# dpbv3_schematic.net
KiCad netlist of a schematic drawn in EasyEDA Pro
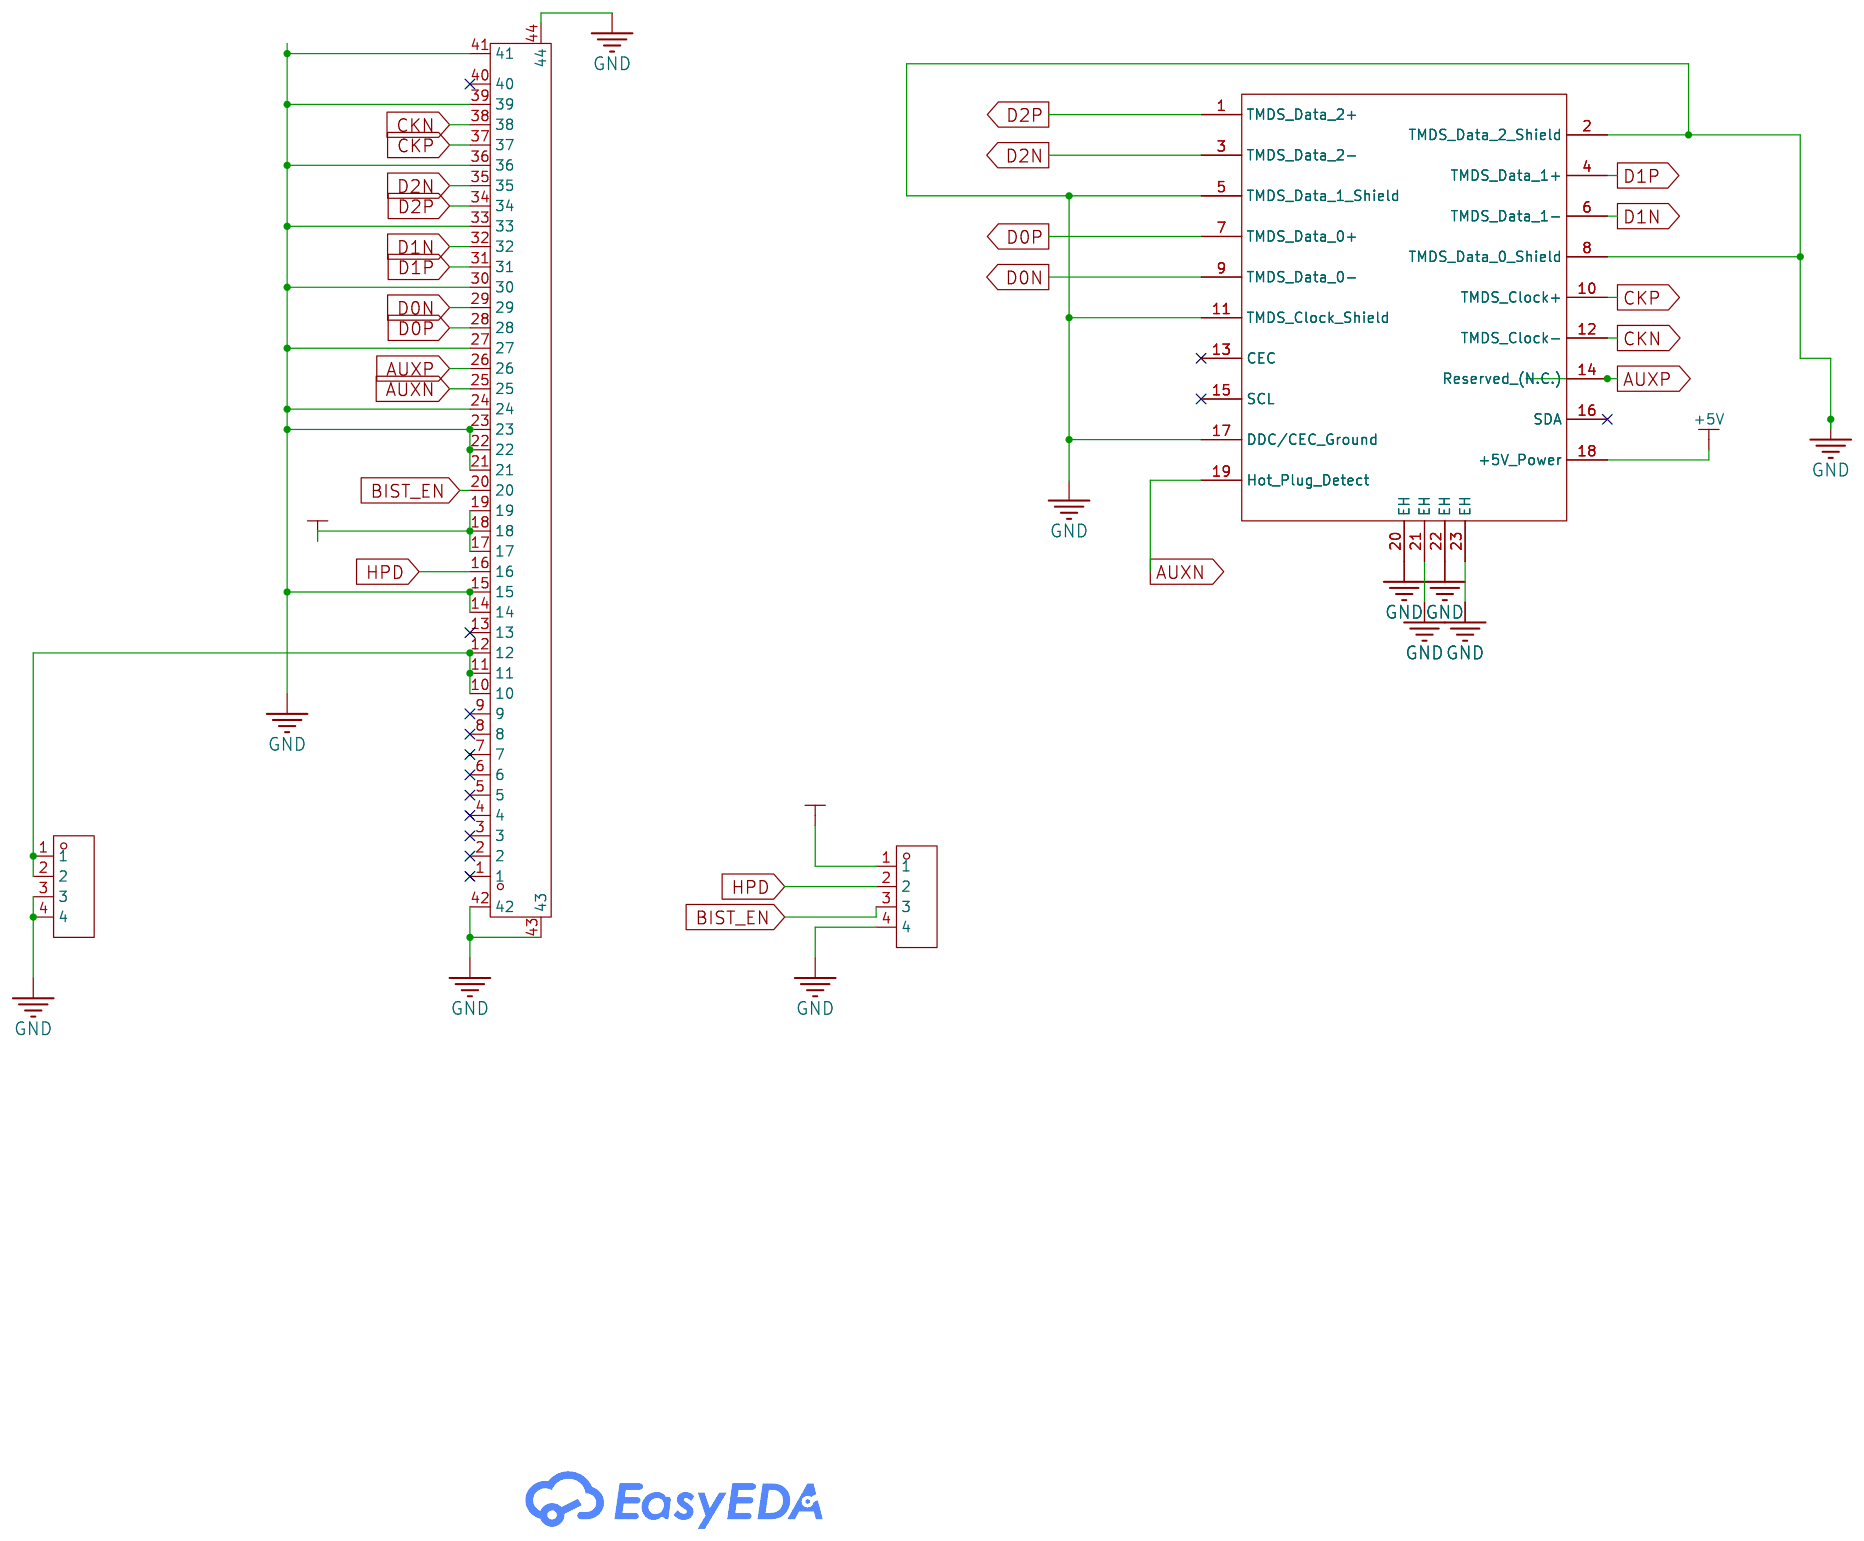
[diagram p0: schematic sheet]

(export (version "E")
  (design (tool "Eeschema 10.0.6"))
  (components
    (comp (ref "CN1")
      (value "20455-040E-76")
      (footprint "easyedapro:CONN-SMD_40P-P-0.50_20455-040E-76")
      (fields (field (name "Manufacturer") "I-PEX(第一精工)"))
      (libsource (lib "easyedapro") (part "20455-040E-76"))
    )
    (comp (ref "CN2")
      (value "HYC109-HDMIA19-160")
      (footprint "easyedapro:HDMI-SMD_HYC109-HDMIA19-160")
      (fields (field (name "Manufacturer") "华宇创"))
      (libsource (lib "easyedapro") (part "HYC109-HDMIA19-160"))
    )
    (comp (ref "H1")
      (value "PZ254V-11-04P")
      (footprint "easyedapro:HDR-TH_4P-P2.54-V-M")
      (fields (field (name "Manufacturer") "XFCN(兴飞)"))
      (libsource (lib "easyedapro") (part "PZ254V-11-04P_C2691448"))
    )
    (comp (ref "H2")
      (value "PZ254V-11-04P")
      (footprint "easyedapro:HDR-TH_4P-P2.54-V-M")
      (fields (field (name "Manufacturer") "XFCN(兴飞)"))
      (libsource (lib "easyedapro") (part "PZ254V-11-04P_C2691448"))
    )
  )
  (nets
    (net (code "1") (name "+3.3V") (class "Default")
      (node (ref "CN1") (pin "17") (pinfunction "17_17") (pintype "unspecified"))
      (node (ref "CN1") (pin "18") (pinfunction "18_18") (pintype "unspecified"))
      (node (ref "CN1") (pin "19") (pinfunction "19_19") (pintype "unspecified"))
      (node (ref "H2") (pin "1") (pinfunction "1_1") (pintype "input"))
    )
    (net (code "2") (name "+5V") (class "Default")
      (node (ref "CN2") (pin "18") (pinfunction "+5V_Power_18") (pintype "unspecified"))
    )
    (net (code "3") (name "AUXN") (class "Default")
      (node (ref "CN1") (pin "25") (pinfunction "25_25") (pintype "unspecified"))
      (node (ref "CN2") (pin "19") (pinfunction "Hot_Plug_Detect_19") (pintype "unspecified"))
    )
    (net (code "4") (name "AUXP") (class "Default")
      (node (ref "CN1") (pin "26") (pinfunction "26_26") (pintype "unspecified"))
      (node (ref "CN2") (pin "14") (pinfunction "Reserved_(N.C.)_14") (pintype "unspecified"))
    )
    (net (code "5") (name "BIST_EN") (class "Default")
      (node (ref "CN1") (pin "20") (pinfunction "20_20") (pintype "unspecified"))
      (node (ref "H2") (pin "3") (pinfunction "3_3") (pintype "input"))
    )
    (net (code "6") (name "CKN") (class "Default")
      (node (ref "CN1") (pin "38") (pinfunction "38_38") (pintype "unspecified"))
      (node (ref "CN2") (pin "12") (pinfunction "TMDS_Clock-_12") (pintype "unspecified"))
    )
    (net (code "7") (name "CKP") (class "Default")
      (node (ref "CN1") (pin "37") (pinfunction "37_37") (pintype "unspecified"))
      (node (ref "CN2") (pin "10") (pinfunction "TMDS_Clock+_10") (pintype "unspecified"))
    )
    (net (code "8") (name "D0N") (class "Default")
      (node (ref "CN1") (pin "29") (pinfunction "29_29") (pintype "unspecified"))
      (node (ref "CN2") (pin "9") (pinfunction "TMDS_Data_0-_9") (pintype "unspecified"))
    )
    (net (code "9") (name "D0P") (class "Default")
      (node (ref "CN1") (pin "28") (pinfunction "28_28") (pintype "unspecified"))
      (node (ref "CN2") (pin "7") (pinfunction "TMDS_Data_0+_7") (pintype "unspecified"))
    )
    (net (code "10") (name "D1N") (class "Default")
      (node (ref "CN1") (pin "32") (pinfunction "32_32") (pintype "unspecified"))
      (node (ref "CN2") (pin "6") (pinfunction "TMDS_Data_1-_6") (pintype "unspecified"))
    )
    (net (code "11") (name "D1P") (class "Default")
      (node (ref "CN1") (pin "31") (pinfunction "31_31") (pintype "unspecified"))
      (node (ref "CN2") (pin "4") (pinfunction "TMDS_Data_1+_4") (pintype "unspecified"))
    )
    (net (code "12") (name "D2N") (class "Default")
      (node (ref "CN1") (pin "35") (pinfunction "35_35") (pintype "unspecified"))
      (node (ref "CN2") (pin "3") (pinfunction "TMDS_Data_2-_3") (pintype "unspecified"))
    )
    (net (code "13") (name "D2P") (class "Default")
      (node (ref "CN1") (pin "34") (pinfunction "34_34") (pintype "unspecified"))
      (node (ref "CN2") (pin "1") (pinfunction "TMDS_Data_2+_1") (pintype "unspecified"))
    )
    (net (code "14") (name "GND") (class "Default")
      (node (ref "CN1") (pin "14") (pinfunction "14_14") (pintype "unspecified"))
      (node (ref "CN1") (pin "15") (pinfunction "15_15") (pintype "unspecified"))
      (node (ref "CN1") (pin "21") (pinfunction "21_21") (pintype "unspecified"))
      (node (ref "CN1") (pin "22") (pinfunction "22_22") (pintype "unspecified"))
      (node (ref "CN1") (pin "23") (pinfunction "23_23") (pintype "unspecified"))
      (node (ref "CN1") (pin "24") (pinfunction "24_24") (pintype "unspecified"))
      (node (ref "CN1") (pin "27") (pinfunction "27_27") (pintype "unspecified"))
      (node (ref "CN1") (pin "30") (pinfunction "30_30") (pintype "unspecified"))
      (node (ref "CN1") (pin "33") (pinfunction "33_33") (pintype "unspecified"))
      (node (ref "CN1") (pin "36") (pinfunction "36_36") (pintype "unspecified"))
      (node (ref "CN1") (pin "39") (pinfunction "39_39") (pintype "unspecified"))
      (node (ref "CN1") (pin "41") (pinfunction "41_41") (pintype "unspecified"))
      (node (ref "CN1") (pin "42") (pinfunction "42_42") (pintype "unspecified"))
      (node (ref "CN1") (pin "43") (pinfunction "43_43") (pintype "unspecified"))
      (node (ref "CN1") (pin "44") (pinfunction "44_44") (pintype "unspecified"))
      (node (ref "CN2") (pin "11") (pinfunction "TMDS_Clock_Shield_11") (pintype "unspecified"))
      (node (ref "CN2") (pin "17") (pinfunction "DDC/CEC_Ground_17") (pintype "unspecified"))
      (node (ref "CN2") (pin "2") (pinfunction "TMDS_Data_2_Shield_2") (pintype "unspecified"))
      (node (ref "CN2") (pin "20") (pinfunction "EH_20") (pintype "unspecified"))
      (node (ref "CN2") (pin "21") (pinfunction "EH_21") (pintype "unspecified"))
      (node (ref "CN2") (pin "22") (pinfunction "EH_22") (pintype "unspecified"))
      (node (ref "CN2") (pin "23") (pinfunction "EH_23") (pintype "unspecified"))
      (node (ref "CN2") (pin "5") (pinfunction "TMDS_Data_1_Shield_5") (pintype "unspecified"))
      (node (ref "CN2") (pin "8") (pinfunction "TMDS_Data_0_Shield_8") (pintype "unspecified"))
      (node (ref "H1") (pin "3") (pinfunction "3_3") (pintype "input"))
      (node (ref "H1") (pin "4") (pinfunction "4_4") (pintype "input"))
      (node (ref "H2") (pin "4") (pinfunction "4_4") (pintype "input"))
    )
    (net (code "15") (name "HPD") (class "Default")
      (node (ref "CN1") (pin "16") (pinfunction "16_16") (pintype "unspecified"))
      (node (ref "H2") (pin "2") (pinfunction "2_2") (pintype "input"))
    )
    (net (code "16") (name "Net-(CN1-Pad10)") (class "Default")
      (node (ref "CN1") (pin "10") (pinfunction "10_10") (pintype "unspecified"))
      (node (ref "CN1") (pin "11") (pinfunction "11_11") (pintype "unspecified"))
      (node (ref "CN1") (pin "12") (pinfunction "12_12") (pintype "unspecified"))
      (node (ref "H1") (pin "1") (pinfunction "1_1") (pintype "input"))
      (node (ref "H1") (pin "2") (pinfunction "2_2") (pintype "input"))
    )
    (net (code "17") (name "unconnected-(CN1-Pad1)") (class "Default")
      (node (ref "CN1") (pin "1") (pinfunction "1_1") (pintype "unspecified+no_connect"))
    )
    (net (code "18") (name "unconnected-(CN1-Pad2)") (class "Default")
      (node (ref "CN1") (pin "2") (pinfunction "2_2") (pintype "unspecified+no_connect"))
    )
    (net (code "19") (name "unconnected-(CN1-Pad3)") (class "Default")
      (node (ref "CN1") (pin "3") (pinfunction "3_3") (pintype "unspecified+no_connect"))
    )
    (net (code "20") (name "unconnected-(CN1-Pad4)") (class "Default")
      (node (ref "CN1") (pin "4") (pinfunction "4_4") (pintype "unspecified+no_connect"))
    )
    (net (code "21") (name "unconnected-(CN1-Pad5)") (class "Default")
      (node (ref "CN1") (pin "5") (pinfunction "5_5") (pintype "unspecified+no_connect"))
    )
    (net (code "22") (name "unconnected-(CN1-Pad6)") (class "Default")
      (node (ref "CN1") (pin "6") (pinfunction "6_6") (pintype "unspecified+no_connect"))
    )
    (net (code "23") (name "unconnected-(CN1-Pad7)") (class "Default")
      (node (ref "CN1") (pin "7") (pinfunction "7_7") (pintype "unspecified+no_connect"))
    )
    (net (code "24") (name "unconnected-(CN1-Pad8)") (class "Default")
      (node (ref "CN1") (pin "8") (pinfunction "8_8") (pintype "unspecified+no_connect"))
    )
    (net (code "25") (name "unconnected-(CN1-Pad9)") (class "Default")
      (node (ref "CN1") (pin "9") (pinfunction "9_9") (pintype "unspecified+no_connect"))
    )
    (net (code "26") (name "unconnected-(CN1-Pad13)") (class "Default")
      (node (ref "CN1") (pin "13") (pinfunction "13_13") (pintype "unspecified+no_connect"))
    )
    (net (code "27") (name "unconnected-(CN1-Pad40)") (class "Default")
      (node (ref "CN1") (pin "40") (pinfunction "40_40") (pintype "unspecified+no_connect"))
    )
    (net (code "28") (name "unconnected-(CN2-CEC-Pad13)") (class "Default")
      (node (ref "CN2") (pin "13") (pinfunction "CEC_13") (pintype "unspecified+no_connect"))
    )
    (net (code "29") (name "unconnected-(CN2-SCL-Pad15)") (class "Default")
      (node (ref "CN2") (pin "15") (pinfunction "SCL_15") (pintype "unspecified+no_connect"))
    )
    (net (code "30") (name "unconnected-(CN2-SDA-Pad16)") (class "Default")
      (node (ref "CN2") (pin "16") (pinfunction "SDA_16") (pintype "unspecified+no_connect"))
    )
  )
)
